# USB_Charger.net
KiCad netlist of a schematic drawn in Altium Designer
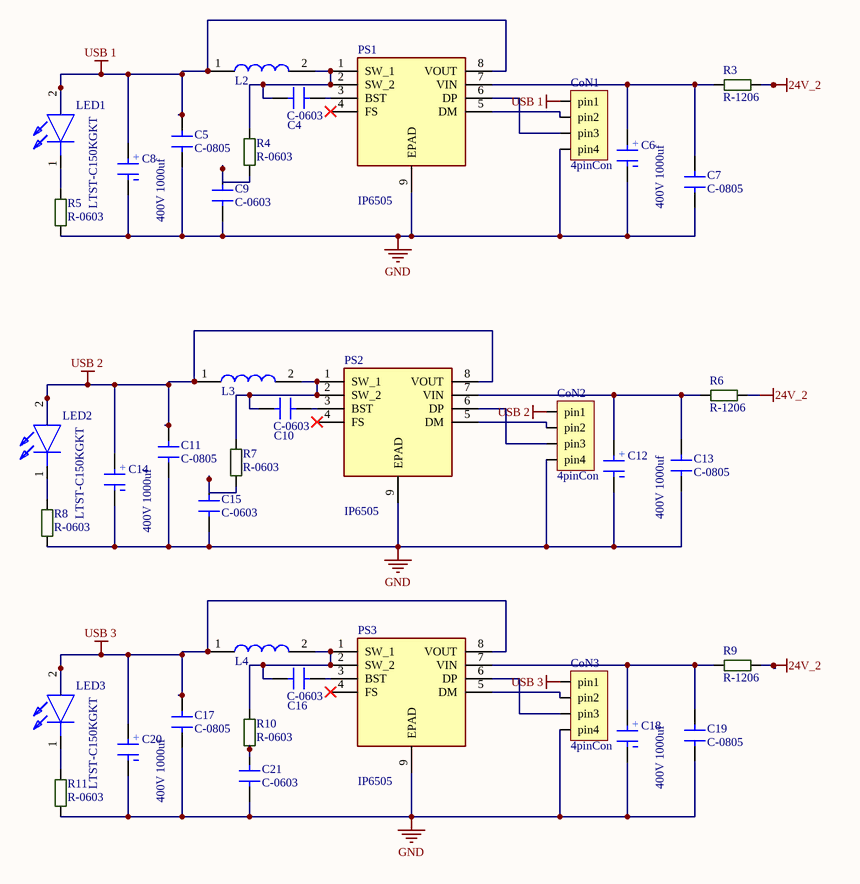
[diagram p0: USB Charger.SchDoc]

(export (version "E")
  (design (tool "Eeschema 10.0.6"))
  (components
    (comp (ref "C4")
      (value "C-0603")
      (footprint "C-0603W")
      (libsource (lib "Charger_SCHLIB") (part "C-0603"))
    )
    (comp (ref "C5")
      (value "C-0805")
      (footprint "C-0805W")
      (libsource (lib "Charger_SCHLIB") (part "C-0805"))
    )
    (comp (ref "C6")
      (value "400V 1000uf")
      (footprint "CAP_EEETC1C331V")
      (fields
        (field (name "MANUFACTURER") "Nichicon")
        (field (name "MANUFACTURER PART NUMBER") "LKS1J472MESZ")
        (field (name "TOLERANCE") "20%")
      )
      (libsource (lib "Schlib1") (part "Aluminum Electrolytic Capacitors"))
    )
    (comp (ref "C7")
      (value "C-0805")
      (footprint "C-0805W")
      (libsource (lib "Charger_SCHLIB") (part "C-0805"))
    )
    (comp (ref "C8")
      (value "400V 1000uf")
      (footprint "CAP_EEETC1C331V")
      (fields
        (field (name "MANUFACTURER") "Nichicon")
        (field (name "MANUFACTURER PART NUMBER") "LKS1J472MESZ")
        (field (name "TOLERANCE") "20%")
      )
      (libsource (lib "Schlib1") (part "Aluminum Electrolytic Capacitors"))
    )
    (comp (ref "C9")
      (value "C-0603")
      (footprint "C-0603W")
      (libsource (lib "Charger_SCHLIB") (part "C-0603"))
    )
    (comp (ref "C10")
      (value "C-0603")
      (footprint "C-0603W")
      (libsource (lib "Charger_SCHLIB") (part "C-0603"))
    )
    (comp (ref "C11")
      (value "C-0805")
      (footprint "C-0805W")
      (libsource (lib "Charger_SCHLIB") (part "C-0805"))
    )
    (comp (ref "C12")
      (value "400V 1000uf")
      (footprint "CAP_EEETC1C331V")
      (fields
        (field (name "MANUFACTURER") "Nichicon")
        (field (name "MANUFACTURER PART NUMBER") "LKS1J472MESZ")
        (field (name "TOLERANCE") "20%")
      )
      (libsource (lib "Schlib1") (part "Aluminum Electrolytic Capacitors"))
    )
    (comp (ref "C13")
      (value "C-0805")
      (footprint "C-0805W")
      (libsource (lib "Charger_SCHLIB") (part "C-0805"))
    )
    (comp (ref "C14")
      (value "400V 1000uf")
      (footprint "CAP_EEETC1C331V")
      (fields
        (field (name "MANUFACTURER") "Nichicon")
        (field (name "MANUFACTURER PART NUMBER") "LKS1J472MESZ")
        (field (name "TOLERANCE") "20%")
      )
      (libsource (lib "Schlib1") (part "Aluminum Electrolytic Capacitors"))
    )
    (comp (ref "C15")
      (value "C-0603")
      (footprint "C-0603W")
      (libsource (lib "Charger_SCHLIB") (part "C-0603"))
    )
    (comp (ref "C16")
      (value "C-0603")
      (footprint "C-0603W")
      (libsource (lib "Charger_SCHLIB") (part "C-0603"))
    )
    (comp (ref "C17")
      (value "C-0805")
      (footprint "C-0805W")
      (libsource (lib "Charger_SCHLIB") (part "C-0805"))
    )
    (comp (ref "C18")
      (value "400V 1000uf")
      (footprint "CAP_EEETC1C331V")
      (fields
        (field (name "MANUFACTURER") "Nichicon")
        (field (name "MANUFACTURER PART NUMBER") "LKS1J472MESZ")
        (field (name "TOLERANCE") "20%")
      )
      (libsource (lib "Schlib1") (part "Aluminum Electrolytic Capacitors"))
    )
    (comp (ref "C19")
      (value "C-0805")
      (footprint "C-0805W")
      (libsource (lib "Charger_SCHLIB") (part "C-0805"))
    )
    (comp (ref "C20")
      (value "400V 1000uf")
      (footprint "CAP_EEETC1C331V")
      (fields
        (field (name "MANUFACTURER") "Nichicon")
        (field (name "MANUFACTURER PART NUMBER") "LKS1J472MESZ")
        (field (name "TOLERANCE") "20%")
      )
      (libsource (lib "Schlib1") (part "Aluminum Electrolytic Capacitors"))
    )
    (comp (ref "C21")
      (value "C-0603")
      (footprint "C-0603W")
      (libsource (lib "Charger_SCHLIB") (part "C-0603"))
    )
    (comp (ref "CoN1") (value "4pinCon") (footprint "4pinCon") (libsource (lib "Schlib1") (part "4pinCon")))
    (comp (ref "CoN2") (value "4pinCon") (footprint "4pinCon") (libsource (lib "Schlib1") (part "4pinCon")))
    (comp (ref "CoN3") (value "4pinCon") (footprint "4pinCon") (libsource (lib "Schlib1") (part "4pinCon")))
    (comp (ref "L2")
      (value "inducter_SMPI06050")
      (footprint "inductor")
      (libsource (lib "Charger_SCHLIB") (part "inducter_SMPI06050"))
    )
    (comp (ref "L3")
      (value "inducter_SMPI06050")
      (footprint "inductor")
      (libsource (lib "Charger_SCHLIB") (part "inducter_SMPI06050"))
    )
    (comp (ref "L4")
      (value "inducter_SMPI06050")
      (footprint "inductor")
      (libsource (lib "Charger_SCHLIB") (part "inducter_SMPI06050"))
    )
    (comp (ref "LED1")
      (value "LTST-C150KGKT")
      (footprint "LED1206")
      (description "LED")
      (fields
        (field (name "MOUSER PART NUMBER") "859-LTST-C150KGKT")
        (field (name "RS PART NUMBER") "6920871")
      )
      (libsource (lib "Charger_SCHLIB") (part "LTST-C150KGKT"))
    )
    (comp (ref "LED2")
      (value "LTST-C150KGKT")
      (footprint "LED1206")
      (description "LED")
      (fields
        (field (name "MOUSER PART NUMBER") "859-LTST-C150KGKT")
        (field (name "RS PART NUMBER") "6920871")
      )
      (libsource (lib "Charger_SCHLIB") (part "LTST-C150KGKT"))
    )
    (comp (ref "LED3")
      (value "LTST-C150KGKT")
      (footprint "LED1206")
      (description "LED")
      (fields
        (field (name "MOUSER PART NUMBER") "859-LTST-C150KGKT")
        (field (name "RS PART NUMBER") "6920871")
      )
      (libsource (lib "Charger_SCHLIB") (part "LTST-C150KGKT"))
    )
    (comp (ref "PS1")
      (value "IP6505")
      (footprint "IP6505")
      (description "Power Supply")
      (libsource (lib "Charger_SCHLIB") (part "IP6505"))
    )
    (comp (ref "PS2")
      (value "IP6505")
      (footprint "IP6505")
      (description "Power Supply")
      (libsource (lib "Charger_SCHLIB") (part "IP6505"))
    )
    (comp (ref "PS3")
      (value "IP6505")
      (footprint "IP6505")
      (description "Power Supply")
      (libsource (lib "Charger_SCHLIB") (part "IP6505"))
    )
    (comp (ref "R3")
      (value "R-1206")
      (footprint "R-1206W")
      (libsource (lib "Charger_SCHLIB") (part "R-1206"))
    )
    (comp (ref "R4")
      (value "R-0603")
      (footprint "R-0603W")
      (libsource (lib "Charger_SCHLIB") (part "R-0603"))
    )
    (comp (ref "R5")
      (value "R-0603")
      (footprint "R-0603W")
      (libsource (lib "Charger_SCHLIB") (part "R-0603"))
    )
    (comp (ref "R6")
      (value "R-1206")
      (footprint "R-1206W")
      (libsource (lib "Charger_SCHLIB") (part "R-1206"))
    )
    (comp (ref "R7")
      (value "R-0603")
      (footprint "R-0603W")
      (libsource (lib "Charger_SCHLIB") (part "R-0603"))
    )
    (comp (ref "R8")
      (value "R-0603")
      (footprint "R-0603W")
      (libsource (lib "Charger_SCHLIB") (part "R-0603"))
    )
    (comp (ref "R9")
      (value "R-1206")
      (footprint "R-1206W")
      (libsource (lib "Charger_SCHLIB") (part "R-1206"))
    )
    (comp (ref "R10")
      (value "R-0603")
      (footprint "R-0603W")
      (libsource (lib "Charger_SCHLIB") (part "R-0603"))
    )
    (comp (ref "R11")
      (value "R-0603")
      (footprint "R-0603W")
      (libsource (lib "Charger_SCHLIB") (part "R-0603"))
    )
  )
  (nets
    (net (code "1") (name "24V_2") (class "Default")
      (node (ref "R3") (pin "1") (pinfunction "1_1") (pintype "passive"))
      (node (ref "R6") (pin "1") (pinfunction "1_1") (pintype "passive"))
      (node (ref "R9") (pin "1") (pinfunction "1_1") (pintype "passive"))
    )
    (net (code "2") (name "GND") (class "Default")
      (node (ref "C11") (pin "1") (pinfunction "1_1") (pintype "passive"))
      (node (ref "C12") (pin "2") (pinfunction "2_2") (pintype "passive"))
      (node (ref "C13") (pin "1") (pinfunction "1_1") (pintype "passive"))
      (node (ref "C14") (pin "2") (pinfunction "2_2") (pintype "passive"))
      (node (ref "C15") (pin "1") (pinfunction "1_1") (pintype "passive"))
      (node (ref "C17") (pin "1") (pinfunction "1_1") (pintype "passive"))
      (node (ref "C18") (pin "2") (pinfunction "2_2") (pintype "passive"))
      (node (ref "C19") (pin "1") (pinfunction "1_1") (pintype "passive"))
      (node (ref "C20") (pin "2") (pinfunction "2_2") (pintype "passive"))
      (node (ref "C21") (pin "1") (pinfunction "1_1") (pintype "passive"))
      (node (ref "C5") (pin "1") (pinfunction "1_1") (pintype "passive"))
      (node (ref "C6") (pin "2") (pinfunction "2_2") (pintype "passive"))
      (node (ref "C7") (pin "1") (pinfunction "1_1") (pintype "passive"))
      (node (ref "C8") (pin "2") (pinfunction "2_2") (pintype "passive"))
      (node (ref "C9") (pin "1") (pinfunction "1_1") (pintype "passive"))
      (node (ref "CoN1") (pin "4") (pinfunction "pin4_4") (pintype "passive"))
      (node (ref "CoN2") (pin "4") (pinfunction "pin4_4") (pintype "passive"))
      (node (ref "CoN3") (pin "4") (pinfunction "pin4_4") (pintype "passive"))
      (node (ref "PS1") (pin "9") (pinfunction "EPAD_9") (pintype "passive"))
      (node (ref "PS2") (pin "9") (pinfunction "EPAD_9") (pintype "passive"))
      (node (ref "PS3") (pin "9") (pinfunction "EPAD_9") (pintype "passive"))
      (node (ref "R11") (pin "1") (pinfunction "1_1") (pintype "passive"))
      (node (ref "R5") (pin "1") (pinfunction "1_1") (pintype "passive"))
      (node (ref "R8") (pin "1") (pinfunction "1_1") (pintype "passive"))
    )
    (net (code "3") (name "Net-(C9-Pad2)") (class "Default")
      (node (ref "C9") (pin "2") (pinfunction "2_2") (pintype "passive"))
      (node (ref "R4") (pin "1") (pinfunction "1_1") (pintype "passive"))
    )
    (net (code "4") (name "Net-(C15-Pad2)") (class "Default")
      (node (ref "C15") (pin "2") (pinfunction "2_2") (pintype "passive"))
      (node (ref "R7") (pin "1") (pinfunction "1_1") (pintype "passive"))
    )
    (net (code "5") (name "Net-(C21-Pad2)") (class "Default")
      (node (ref "C21") (pin "2") (pinfunction "2_2") (pintype "passive"))
      (node (ref "R10") (pin "1") (pinfunction "1_1") (pintype "passive"))
    )
    (net (code "6") (name "Net-(CoN1-pin2)") (class "Default")
      (node (ref "CoN1") (pin "2") (pinfunction "pin2_2") (pintype "passive"))
      (node (ref "PS1") (pin "5") (pinfunction "DM_5") (pintype "passive"))
    )
    (net (code "7") (name "Net-(CoN1-pin3)") (class "Default")
      (node (ref "CoN1") (pin "3") (pinfunction "pin3_3") (pintype "passive"))
      (node (ref "PS1") (pin "6") (pinfunction "DP_6") (pintype "passive"))
    )
    (net (code "8") (name "Net-(CoN2-pin2)") (class "Default")
      (node (ref "CoN2") (pin "2") (pinfunction "pin2_2") (pintype "passive"))
      (node (ref "PS2") (pin "5") (pinfunction "DM_5") (pintype "passive"))
    )
    (net (code "9") (name "Net-(CoN2-pin3)") (class "Default")
      (node (ref "CoN2") (pin "3") (pinfunction "pin3_3") (pintype "passive"))
      (node (ref "PS2") (pin "6") (pinfunction "DP_6") (pintype "passive"))
    )
    (net (code "10") (name "Net-(CoN3-pin2)") (class "Default")
      (node (ref "CoN3") (pin "2") (pinfunction "pin2_2") (pintype "passive"))
      (node (ref "PS3") (pin "5") (pinfunction "DM_5") (pintype "passive"))
    )
    (net (code "11") (name "Net-(CoN3-pin3)") (class "Default")
      (node (ref "CoN3") (pin "3") (pinfunction "pin3_3") (pintype "passive"))
      (node (ref "PS3") (pin "6") (pinfunction "DP_6") (pintype "passive"))
    )
    (net (code "12") (name "Net-(LED1-K)") (class "Default")
      (node (ref "LED1") (pin "1") (pinfunction "K_1") (pintype "passive"))
      (node (ref "R5") (pin "2") (pinfunction "2_2") (pintype "passive"))
    )
    (net (code "13") (name "Net-(LED2-K)") (class "Default")
      (node (ref "LED2") (pin "1") (pinfunction "K_1") (pintype "passive"))
      (node (ref "R8") (pin "2") (pinfunction "2_2") (pintype "passive"))
    )
    (net (code "14") (name "Net-(LED3-K)") (class "Default")
      (node (ref "LED3") (pin "1") (pinfunction "K_1") (pintype "passive"))
      (node (ref "R11") (pin "2") (pinfunction "2_2") (pintype "passive"))
    )
    (net (code "15") (name "Net-(PS1-BST)") (class "Default")
      (node (ref "C4") (pin "1") (pinfunction "1_1") (pintype "passive"))
      (node (ref "PS1") (pin "3") (pinfunction "BST_3") (pintype "passive"))
    )
    (net (code "16") (name "Net-(PS1-SW_1)") (class "Default")
      (node (ref "C4") (pin "2") (pinfunction "2_2") (pintype "passive"))
      (node (ref "L2") (pin "2") (pinfunction "2_2") (pintype "passive"))
      (node (ref "PS1") (pin "1") (pinfunction "SW_1_1") (pintype "passive"))
      (node (ref "PS1") (pin "2") (pinfunction "SW_2_2") (pintype "passive"))
      (node (ref "R4") (pin "2") (pinfunction "2_2") (pintype "passive"))
    )
    (net (code "17") (name "Net-(PS1-VIN)") (class "Default")
      (node (ref "C6") (pin "1") (pinfunction "1_1") (pintype "passive"))
      (node (ref "C7") (pin "2") (pinfunction "2_2") (pintype "passive"))
      (node (ref "PS1") (pin "7") (pinfunction "VIN_7") (pintype "passive"))
      (node (ref "R3") (pin "2") (pinfunction "2_2") (pintype "passive"))
    )
    (net (code "18") (name "Net-(PS2-BST)") (class "Default")
      (node (ref "C10") (pin "1") (pinfunction "1_1") (pintype "passive"))
      (node (ref "PS2") (pin "3") (pinfunction "BST_3") (pintype "passive"))
    )
    (net (code "19") (name "Net-(PS2-SW_1)") (class "Default")
      (node (ref "C10") (pin "2") (pinfunction "2_2") (pintype "passive"))
      (node (ref "L3") (pin "2") (pinfunction "2_2") (pintype "passive"))
      (node (ref "PS2") (pin "1") (pinfunction "SW_1_1") (pintype "passive"))
      (node (ref "PS2") (pin "2") (pinfunction "SW_2_2") (pintype "passive"))
      (node (ref "R7") (pin "2") (pinfunction "2_2") (pintype "passive"))
    )
    (net (code "20") (name "Net-(PS2-VIN)") (class "Default")
      (node (ref "C12") (pin "1") (pinfunction "1_1") (pintype "passive"))
      (node (ref "C13") (pin "2") (pinfunction "2_2") (pintype "passive"))
      (node (ref "PS2") (pin "7") (pinfunction "VIN_7") (pintype "passive"))
      (node (ref "R6") (pin "2") (pinfunction "2_2") (pintype "passive"))
    )
    (net (code "21") (name "Net-(PS3-BST)") (class "Default")
      (node (ref "C16") (pin "1") (pinfunction "1_1") (pintype "passive"))
      (node (ref "PS3") (pin "3") (pinfunction "BST_3") (pintype "passive"))
    )
    (net (code "22") (name "Net-(PS3-SW_1)") (class "Default")
      (node (ref "C16") (pin "2") (pinfunction "2_2") (pintype "passive"))
      (node (ref "L4") (pin "2") (pinfunction "2_2") (pintype "passive"))
      (node (ref "PS3") (pin "1") (pinfunction "SW_1_1") (pintype "passive"))
      (node (ref "PS3") (pin "2") (pinfunction "SW_2_2") (pintype "passive"))
      (node (ref "R10") (pin "2") (pinfunction "2_2") (pintype "passive"))
    )
    (net (code "23") (name "Net-(PS3-VIN)") (class "Default")
      (node (ref "C18") (pin "1") (pinfunction "1_1") (pintype "passive"))
      (node (ref "C19") (pin "2") (pinfunction "2_2") (pintype "passive"))
      (node (ref "PS3") (pin "7") (pinfunction "VIN_7") (pintype "passive"))
      (node (ref "R9") (pin "2") (pinfunction "2_2") (pintype "passive"))
    )
    (net (code "24") (name "USB 1") (class "Default")
      (node (ref "C5") (pin "2") (pinfunction "2_2") (pintype "passive"))
      (node (ref "C8") (pin "1") (pinfunction "1_1") (pintype "passive"))
      (node (ref "CoN1") (pin "1") (pinfunction "pin1_1") (pintype "passive"))
      (node (ref "L2") (pin "1") (pinfunction "1_1") (pintype "passive"))
      (node (ref "LED1") (pin "2") (pinfunction "A_2") (pintype "passive"))
      (node (ref "PS1") (pin "8") (pinfunction "VOUT_8") (pintype "passive"))
    )
    (net (code "25") (name "USB 2") (class "Default")
      (node (ref "C11") (pin "2") (pinfunction "2_2") (pintype "passive"))
      (node (ref "C14") (pin "1") (pinfunction "1_1") (pintype "passive"))
      (node (ref "CoN2") (pin "1") (pinfunction "pin1_1") (pintype "passive"))
      (node (ref "L3") (pin "1") (pinfunction "1_1") (pintype "passive"))
      (node (ref "LED2") (pin "2") (pinfunction "A_2") (pintype "passive"))
      (node (ref "PS2") (pin "8") (pinfunction "VOUT_8") (pintype "passive"))
    )
    (net (code "26") (name "USB 3") (class "Default")
      (node (ref "C17") (pin "2") (pinfunction "2_2") (pintype "passive"))
      (node (ref "C20") (pin "1") (pinfunction "1_1") (pintype "passive"))
      (node (ref "CoN3") (pin "1") (pinfunction "pin1_1") (pintype "passive"))
      (node (ref "L4") (pin "1") (pinfunction "1_1") (pintype "passive"))
      (node (ref "LED3") (pin "2") (pinfunction "A_2") (pintype "passive"))
      (node (ref "PS3") (pin "8") (pinfunction "VOUT_8") (pintype "passive"))
    )
    (net (code "27") (name "unconnected-(PS1-FS-Pad4)") (class "Default")
      (node (ref "PS1") (pin "4") (pinfunction "FS_4") (pintype "passive+no_connect"))
    )
    (net (code "28") (name "unconnected-(PS2-FS-Pad4)") (class "Default")
      (node (ref "PS2") (pin "4") (pinfunction "FS_4") (pintype "passive+no_connect"))
    )
    (net (code "29") (name "unconnected-(PS3-FS-Pad4)") (class "Default")
      (node (ref "PS3") (pin "4") (pinfunction "FS_4") (pintype "passive+no_connect"))
    )
  )
)
